# pc_healthypi_move_nRF5340_v3_0.net
KiCad netlist of a schematic drawn in EAGLE
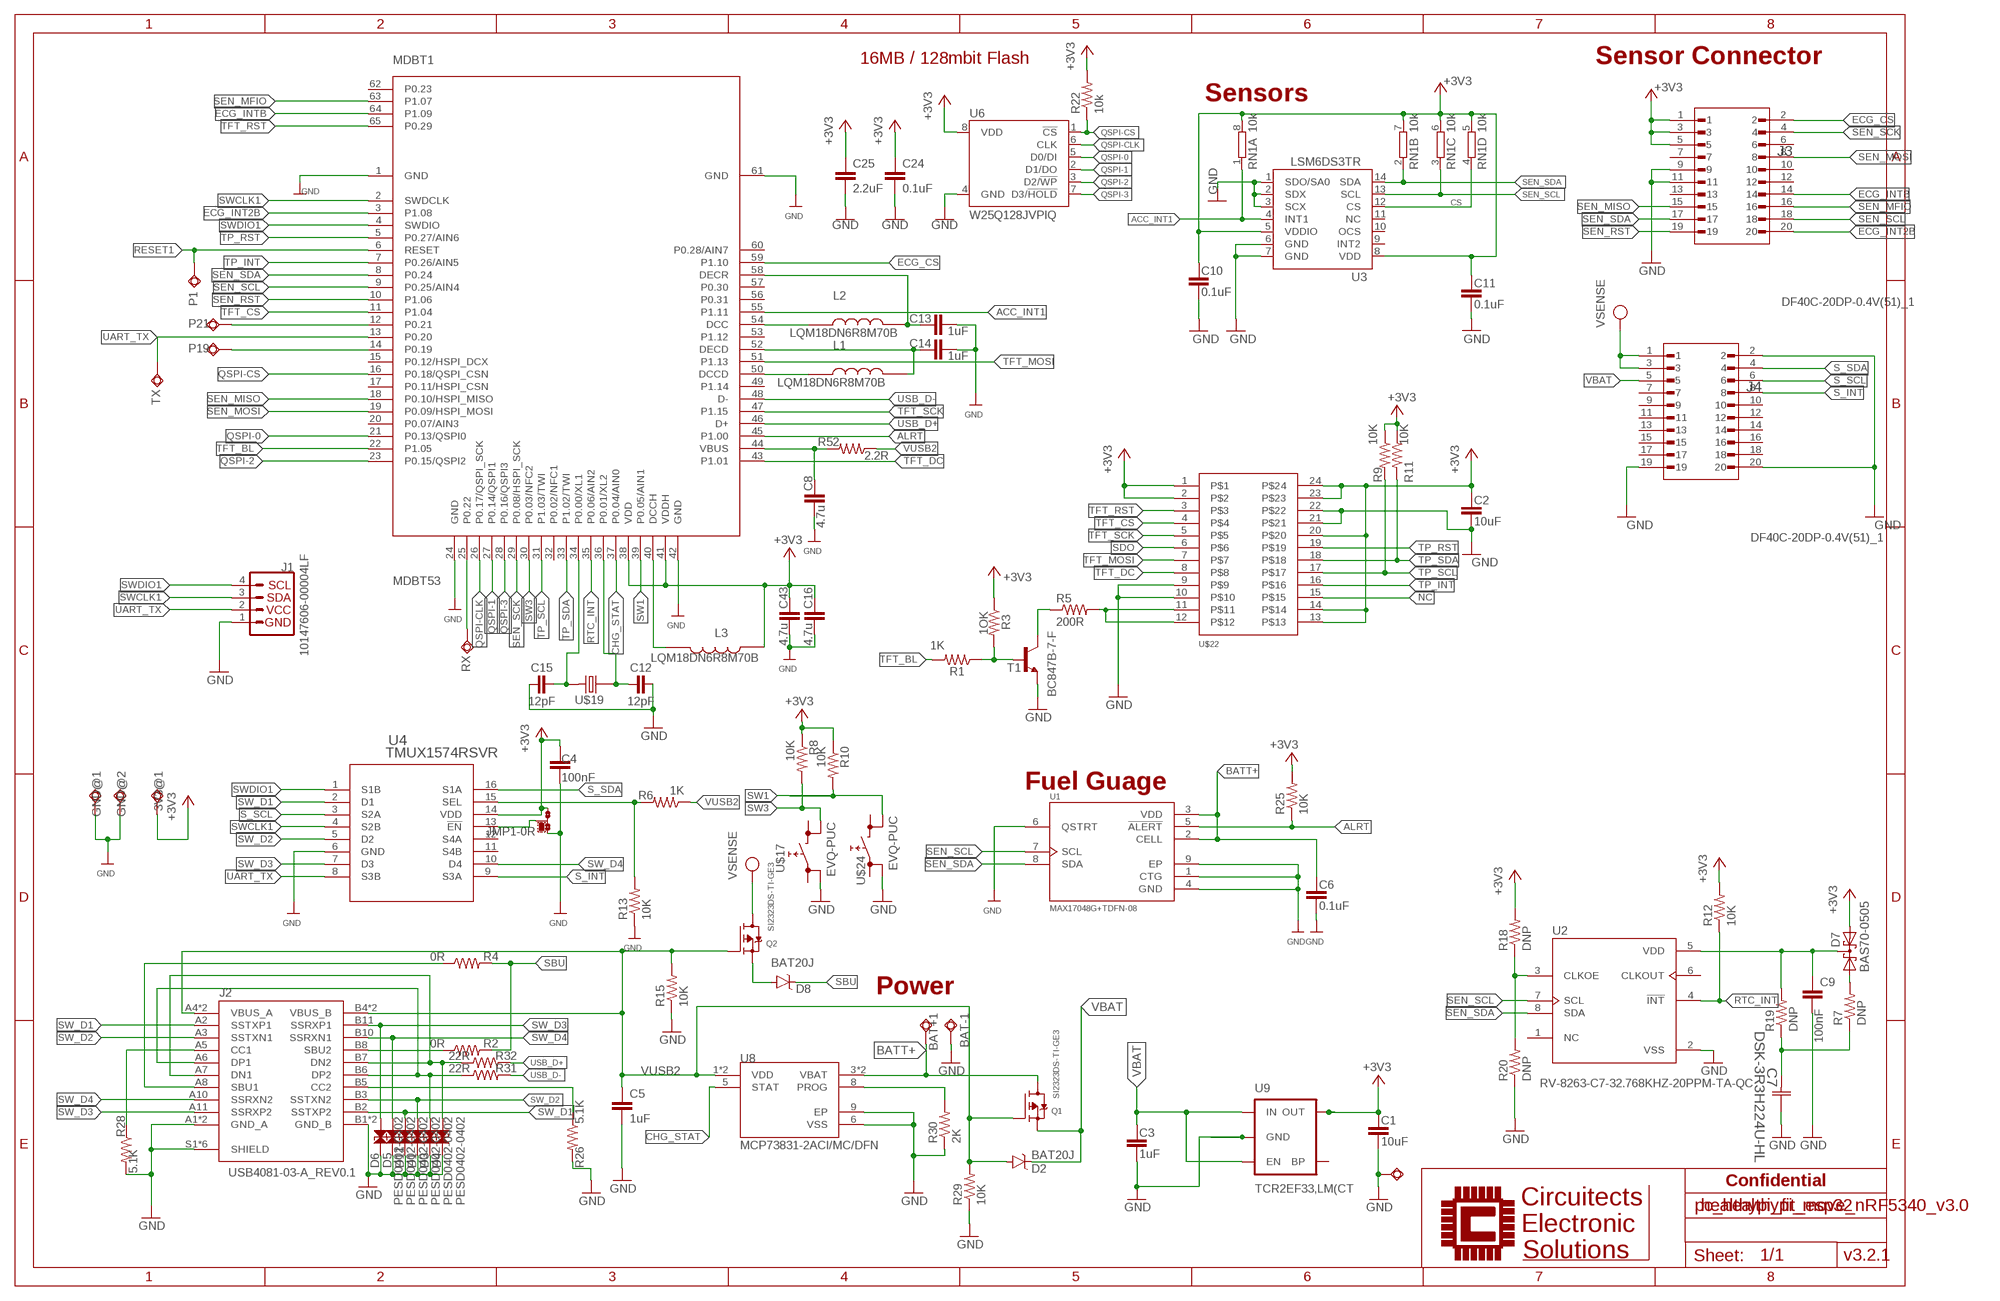
[diagram p0: schematic, sheet 1]

(export (version "E")
  (design (tool "Eeschema 10.0.6"))
  (components
    (comp (ref "3V3@1")
      (value "TPSQTP13SQ")
      (footprint "eagle-import:TP13SQ")
      (libsource (lib "eagle-import") (part "TPSQTP13SQ"))
    )
    (comp (ref "BAT+1")
      (value "TPSQTP13SQ")
      (footprint "eagle-import:TP13SQ")
      (libsource (lib "eagle-import") (part "TPSQTP13SQ"))
    )
    (comp (ref "BAT-1")
      (value "TPSQTP13SQ")
      (footprint "eagle-import:TP13SQ")
      (libsource (lib "eagle-import") (part "TPSQTP13SQ"))
    )
    (comp (ref "C1")
      (value "10uF")
      (footprint "eagle-import:0603@1")
      (libsource (lib "eagle-import") (part "0.1UF-0603-100V-10%"))
    )
    (comp (ref "C2")
      (value "10uF")
      (footprint "eagle-import:0603@1")
      (libsource (lib "eagle-import") (part "0.1UF-0603-100V-10%"))
    )
    (comp (ref "C3")
      (value "1uF")
      (footprint "eagle-import:0402-TIGHT")
      (libsource (lib "eagle-import") (part "0.1UF-0402T-6.3V-10%-X7R"))
    )
    (comp (ref "C4")
      (value "100nF")
      (footprint "eagle-import:0402-TIGHT")
      (libsource (lib "eagle-import") (part "2.2UF-0402_TIGHT-10V-10%-X5R"))
    )
    (comp (ref "C5")
      (value "1uF")
      (footprint "eagle-import:0402-TIGHT")
      (libsource (lib "eagle-import") (part "2.2UF-0402_TIGHT-10V-10%-X5R"))
    )
    (comp (ref "C6")
      (value "0.1uF")
      (footprint "eagle-import:0402-TIGHT")
      (libsource (lib "eagle-import") (part "0.1UF-0402T-6.3V-10%-X7R"))
    )
    (comp (ref "C7")
      (value "DSK-3R3H224U-HL")
      (footprint "eagle-import:CAP_DSK-3R3H224U-HL_ELN")
      (fields (field (name "COPYRIGHT") "Copyright (C) 2023 Ultra Librarian. All rights reserved."))
      (libsource (lib "eagle-import") (part "DSK-3R3H224U-HL"))
    )
    (comp (ref "C8")
      (value "4.7u")
      (footprint "eagle-import:C0402")
      (libsource (lib "eagle-import") (part "C-EUC0402"))
    )
    (comp (ref "C9")
      (value "100nF")
      (footprint "eagle-import:C0402")
      (libsource (lib "eagle-import") (part "C-EUC0402"))
    )
    (comp (ref "C10")
      (value "0.1uF")
      (footprint "eagle-import:0402-TIGHT")
      (libsource (lib "eagle-import") (part "0.1UF-0402T-6.3V-10%-X7R"))
    )
    (comp (ref "C11")
      (value "0.1uF")
      (footprint "eagle-import:0402-TIGHT")
      (libsource (lib "eagle-import") (part "0.1UF-0402T-6.3V-10%-X7R"))
    )
    (comp (ref "C12")
      (value "12pF")
      (footprint "eagle-import:C0402")
      (libsource (lib "eagle-import") (part "CAPACITORS-0402"))
    )
    (comp (ref "C13")
      (value "1uF")
      (footprint "eagle-import:0402-TIGHT")
      (libsource (lib "eagle-import") (part "2.2UF-0402_TIGHT-10V-10%-X5R"))
    )
    (comp (ref "C14")
      (value "1uF")
      (footprint "eagle-import:0402-TIGHT")
      (libsource (lib "eagle-import") (part "2.2UF-0402_TIGHT-10V-10%-X5R"))
    )
    (comp (ref "C15")
      (value "12pF")
      (footprint "eagle-import:C0402")
      (libsource (lib "eagle-import") (part "CAPACITORS-0402"))
    )
    (comp (ref "C16")
      (value "4.7u")
      (footprint "eagle-import:C0402")
      (libsource (lib "eagle-import") (part "C-EUC0402"))
    )
    (comp (ref "C24")
      (value "0.1uF")
      (footprint "eagle-import:0402-TIGHT")
      (libsource (lib "eagle-import") (part "0.1UF-0402T-6.3V-10%-X7R"))
    )
    (comp (ref "C25")
      (value "2.2uF")
      (footprint "eagle-import:0402-TIGHT")
      (libsource (lib "eagle-import") (part "2.2UF-0402_TIGHT-10V-10%-X5R"))
    )
    (comp (ref "C43")
      (value "4.7u")
      (footprint "eagle-import:C0402")
      (libsource (lib "eagle-import") (part "C-EUC0402"))
    )
    (comp (ref "D1")
      (value "PESD0402-0402")
      (footprint "eagle-import:0402")
      (fields
        (field (name "DIGIKEY_PART") "PESD0402-140CT-ND")
        (field (name "MOUSE_PART") "650-PESD0402-140")
      )
      (libsource (lib "eagle-import") (part "PESD0402-0402"))
    )
    (comp (ref "D2")
      (value "BAT20J")
      (footprint "eagle-import:SOD-323")
      (libsource (lib "eagle-import") (part "DIODE-SCHOTTKY-BAT20J"))
    )
    (comp (ref "D3")
      (value "PESD0402-0402")
      (footprint "eagle-import:0402")
      (fields
        (field (name "DIGIKEY_PART") "PESD0402-140CT-ND")
        (field (name "MOUSE_PART") "650-PESD0402-140")
      )
      (libsource (lib "eagle-import") (part "PESD0402-0402"))
    )
    (comp (ref "D4")
      (value "PESD0402-0402")
      (footprint "eagle-import:0402")
      (fields
        (field (name "DIGIKEY_PART") "PESD0402-140CT-ND")
        (field (name "MOUSE_PART") "650-PESD0402-140")
      )
      (libsource (lib "eagle-import") (part "PESD0402-0402"))
    )
    (comp (ref "D5")
      (value "PESD0402-0402")
      (footprint "eagle-import:0402")
      (fields
        (field (name "DIGIKEY_PART") "PESD0402-140CT-ND")
        (field (name "MOUSE_PART") "650-PESD0402-140")
      )
      (libsource (lib "eagle-import") (part "PESD0402-0402"))
    )
    (comp (ref "D6")
      (value "PESD0402-0402")
      (footprint "eagle-import:0402")
      (fields
        (field (name "DIGIKEY_PART") "PESD0402-140CT-ND")
        (field (name "MOUSE_PART") "650-PESD0402-140")
      )
      (libsource (lib "eagle-import") (part "PESD0402-0402"))
    )
    (comp (ref "D7")
      (value "BAS70-0505")
      (footprint "eagle-import:SOT23")
      (fields (field (name "MF") "Diotec") (field (name "MP") "BAS70-05"))
      (libsource (lib "eagle-import") (part "BAS70-0505"))
    )
    (comp (ref "D8")
      (value "BAT20J")
      (footprint "eagle-import:SOD-323")
      (libsource (lib "eagle-import") (part "DIODE-SCHOTTKY-BAT20J"))
    )
    (comp (ref "D11")
      (value "PESD0402-0402")
      (footprint "eagle-import:0402")
      (fields
        (field (name "DIGIKEY_PART") "PESD0402-140CT-ND")
        (field (name "MOUSE_PART") "650-PESD0402-140")
      )
      (libsource (lib "eagle-import") (part "PESD0402-0402"))
    )
    (comp (ref "GND@1")
      (value "TPSQTP13SQ")
      (footprint "eagle-import:TP13SQ")
      (libsource (lib "eagle-import") (part "TPSQTP13SQ"))
    )
    (comp (ref "GND@2")
      (value "TPSQTP13SQ")
      (footprint "eagle-import:TP13SQ")
      (libsource (lib "eagle-import") (part "TPSQTP13SQ"))
    )
    (comp (ref "J1")
      (value "10147606-00004LF")
      (footprint "eagle-import:JST04_1MM_RA")
      (libsource (lib "eagle-import") (part "QWIIC_CONNECTORJS-1MM"))
    )
    (comp (ref "J2")
      (value "USB4081-03-A_REV0.1")
      (footprint "eagle-import:GCT_USB4081-03-A_REV0.1")
      (fields (field (name "MF") "Global Connector Technology") (field (name "MP") "USB4081-03-A"))
      (libsource (lib "eagle-import") (part "USB4081-03-A_REV0.1"))
    )
    (comp (ref "J3")
      (value "DF40C-20DP-0.4V(51)_1")
      (footprint "eagle-import:HRS_DF40C-20DP-0.4V(51)")
      (fields (field (name "MANUFACTURER") "Hirose Electric"))
      (libsource (lib "eagle-import") (part "DF40C-20DP-0.4V(51)_1"))
    )
    (comp (ref "J4")
      (value "DF40C-20DP-0.4V(51)_1")
      (footprint "eagle-import:HRS_DF40C-20DP-0.4V(51)")
      (fields (field (name "MANUFACTURER") "Hirose Electric"))
      (libsource (lib "eagle-import") (part "DF40C-20DP-0.4V(51)_1"))
    )
    (comp (ref "JMP1")
      (value "0R-JUMPB")
      (footprint "eagle-import:B0R-JMP")
      (libsource (lib "eagle-import") (part "0R-JUMPB"))
    )
    (comp (ref "L1")
      (value "LQM18DN6R8M70B")
      (footprint "eagle-import:INDC1608X95N")
      (fields (field (name "MF") "Murata"))
      (libsource (lib "eagle-import") (part "LQM18DN6R8M70B"))
    )
    (comp (ref "L2")
      (value "LQM18DN6R8M70B")
      (footprint "eagle-import:INDC1608X95N")
      (fields (field (name "MF") "Murata"))
      (libsource (lib "eagle-import") (part "LQM18DN6R8M70B"))
    )
    (comp (ref "L3")
      (value "LQM18DN6R8M70B")
      (footprint "eagle-import:INDC1608X95N")
      (fields (field (name "MF") "Murata"))
      (libsource (lib "eagle-import") (part "LQM18DN6R8M70B"))
    )
    (comp (ref "MDBT1")
      (value "MDBT53")
      (footprint "eagle-import:MDBT53")
      (libsource (lib "eagle-import") (part "MDBT53"))
    )
    (comp (ref "P1")
      (value "TPSQTP13SQ")
      (footprint "eagle-import:TP13SQ")
      (libsource (lib "eagle-import") (part "TPSQTP13SQ"))
    )
    (comp (ref "P19")
      (value "TPSQTP13SQ")
      (footprint "eagle-import:TP13SQ")
      (libsource (lib "eagle-import") (part "TPSQTP13SQ"))
    )
    (comp (ref "P21")
      (value "TPSQTP13SQ")
      (footprint "eagle-import:TP13SQ")
      (libsource (lib "eagle-import") (part "TPSQTP13SQ"))
    )
    (comp (ref "Q1")
      (value "SI2323DS-TI-GE3")
      (footprint "eagle-import:SOT23-R")
      (libsource (lib "eagle-import") (part "MOSFET-P"))
    )
    (comp (ref "Q2")
      (value "SI2323DS-TI-GE3")
      (footprint "eagle-import:SOT23-R")
      (libsource (lib "eagle-import") (part "MOSFET-P"))
    )
    (comp (ref "R1")
      (value "200")
      (footprint "eagle-import:R0402")
      (libsource (lib "eagle-import") (part "R-US_R0402"))
    )
    (comp (ref "R2")
      (value "0R")
      (footprint "eagle-import:0402-RES")
      (libsource (lib "eagle-import") (part "RESISTOR0402-RES"))
    )
    (comp (ref "R3")
      (value "200")
      (footprint "eagle-import:R0402")
      (libsource (lib "eagle-import") (part "R-US_R0402"))
    )
    (comp (ref "R4")
      (value "0R")
      (footprint "eagle-import:0402-RES")
      (libsource (lib "eagle-import") (part "RESISTOR0402-RES"))
    )
    (comp (ref "R5")
      (value "200R")
      (footprint "eagle-import:R0402")
      (libsource (lib "eagle-import") (part "R-US_R0402"))
    )
    (comp (ref "R6")
      (value "1K")
      (footprint "eagle-import:0402-RES")
      (libsource (lib "eagle-import") (part "RESISTOR0402-RES"))
    )
    (comp (ref "R7")
      (value "DNP")
      (footprint "eagle-import:R0402")
      (libsource (lib "eagle-import") (part "R-US_R0402"))
    )
    (comp (ref "R8")
      (value "10K")
      (footprint "eagle-import:R0402")
      (libsource (lib "eagle-import") (part "R-US_R0402"))
    )
    (comp (ref "R9")
      (value "10K")
      (footprint "eagle-import:R0402")
      (libsource (lib "eagle-import") (part "R-US_R0402"))
    )
    (comp (ref "R10")
      (value "10K")
      (footprint "eagle-import:R0402")
      (libsource (lib "eagle-import") (part "R-US_R0402"))
    )
    (comp (ref "R11")
      (value "10K")
      (footprint "eagle-import:R0402")
      (libsource (lib "eagle-import") (part "R-US_R0402"))
    )
    (comp (ref "R12")
      (value "10K")
      (footprint "eagle-import:R0402")
      (libsource (lib "eagle-import") (part "R-US_R0402"))
    )
    (comp (ref "R13")
      (value "10K")
      (footprint "eagle-import:R0402")
      (libsource (lib "eagle-import") (part "R-US_R0402"))
    )
    (comp (ref "R15")
      (value "10K")
      (footprint "eagle-import:R0402")
      (libsource (lib "eagle-import") (part "R-US_R0402"))
    )
    (comp (ref "R18")
      (value "DNP")
      (footprint "eagle-import:R0402")
      (libsource (lib "eagle-import") (part "R-US_R0402"))
    )
    (comp (ref "R19")
      (value "DNP")
      (footprint "eagle-import:R0402")
      (libsource (lib "eagle-import") (part "R-US_R0402"))
    )
    (comp (ref "R20")
      (value "DNP")
      (footprint "eagle-import:R0402")
      (libsource (lib "eagle-import") (part "R-US_R0402"))
    )
    (comp (ref "R22")
      (value "10k")
      (footprint "eagle-import:R0402")
      (libsource (lib "eagle-import") (part "R-US_R0402"))
    )
    (comp (ref "R25")
      (value "10K")
      (footprint "eagle-import:0402-RES")
      (libsource (lib "eagle-import") (part "RESISTOR0402-RES"))
    )
    (comp (ref "R26")
      (value "5.1K")
      (footprint "eagle-import:0402-RES")
      (libsource (lib "eagle-import") (part "RESISTOR0402-RES"))
    )
    (comp (ref "R28")
      (value "5.1K")
      (footprint "eagle-import:0402-RES")
      (libsource (lib "eagle-import") (part "RESISTOR0402-RES"))
    )
    (comp (ref "R29")
      (value "10K")
      (footprint "eagle-import:R0402")
      (libsource (lib "eagle-import") (part "R-US_R0402"))
    )
    (comp (ref "R30")
      (value "2K")
      (footprint "eagle-import:R0402")
      (libsource (lib "eagle-import") (part "R-US_R0402"))
    )
    (comp (ref "R31")
      (value "22R")
      (footprint "eagle-import:0402-RES")
      (libsource (lib "eagle-import") (part "RESISTOR0402-RES"))
    )
    (comp (ref "R32")
      (value "22R")
      (footprint "eagle-import:0402-RES")
      (libsource (lib "eagle-import") (part "RESISTOR0402-RES"))
    )
    (comp (ref "R52")
      (value "2.2R")
      (footprint "eagle-import:0402-RES")
      (libsource (lib "eagle-import") (part "RESISTOR0402-RES"))
    )
    (comp (ref "RN1")
      (value "10k")
      (footprint "eagle-import:4X0402ARV341")
      (libsource (lib "eagle-import") (part "4R-N0402ARV341"))
    )
    (comp (ref "RX")
      (value "TPSQTP13SQ")
      (footprint "eagle-import:TP13SQ")
      (libsource (lib "eagle-import") (part "TPSQTP13SQ"))
    )
    (comp (ref "SWIO6")
      (value "TPSQTP11R")
      (footprint "eagle-import:TP11R")
      (libsource (lib "eagle-import") (part "TPSQTP11R"))
    )
    (comp (ref "T1")
      (value "BC847B-7-F")
      (footprint "eagle-import:SOT23-BEC")
      (libsource (lib "eagle-import") (part "-NPN-SOT23-BECMMBT2222ALT1"))
    )
    (comp (ref "TX")
      (value "TPSQTP13SQ")
      (footprint "eagle-import:TP13SQ")
      (libsource (lib "eagle-import") (part "TPSQTP13SQ"))
    )
    (comp (ref "U$17")
      (value "EVQ-PUC")
      (footprint "eagle-import:EVQ-PUC")
      (libsource (lib "eagle-import") (part "EVQ-PUC"))
    )
    (comp (ref "U$19")
      (value "520-327-12.5-34B(32.768KHZ)")
      (footprint "eagle-import:ECX-31B")
      (libsource (lib "eagle-import") (part "ECS-X-34B"))
    )
    (comp (ref "U$22")
      (value "AXT524124")
      (footprint "eagle-import:AXT524124")
      (libsource (lib "eagle-import") (part "AXT524124"))
    )
    (comp (ref "U$24")
      (value "EVQ-PUC")
      (footprint "eagle-import:EVQ-PUC")
      (libsource (lib "eagle-import") (part "EVQ-PUC"))
    )
    (comp (ref "U1")
      (value "MAX17048G+TDFN-08")
      (footprint "eagle-import:SON50P200X200X80-9N")
      (fields (field (name "MF") "Analog Devices") (field (name "MP") "MAX17048G+"))
      (libsource (lib "eagle-import") (part "MAX17048G+TDFN-08"))
    )
    (comp (ref "U2")
      (value "RV-8263-C7-32.768KHZ-20PPM-TA-QC")
      (footprint "eagle-import:IC_RV-8263-C7-32.768KHZ-20PPM-TA-QC")
      (fields (field (name "MF") "Micro Crystal"))
      (libsource (lib "eagle-import") (part "RV-8263-C7-32.768KHZ-20PPM-TA-QC"))
    )
    (comp (ref "U3")
      (value "LSM6DS3TR")
      (footprint "eagle-import:LGA14L")
      (libsource (lib "eagle-import") (part "LSM6DS3"))
    )
    (comp (ref "U4")
      (value "TMUX1574RSVR")
      (footprint "eagle-import:RSV16_TEX")
      (fields (field (name "COPYRIGHT") "Copyright (C) 2024 Ultra Librarian. All rights reserved."))
      (libsource (lib "eagle-import") (part "TMUX1574RSVR"))
    )
    (comp (ref "U6")
      (value "W25Q128JVPIQ")
      (footprint "eagle-import:WSON-8-6X5-SKINNY_CENTERPAD")
      (libsource (lib "eagle-import") (part "W25QXX128MBIT-6X5-SKINNY_CENTER"))
    )
    (comp (ref "U8")
      (value "MCP73831-2ACI/MC/DFN")
      (footprint "eagle-import:SON50P200X300X100-9N")
      (fields (field (name "MF") "Microchip Technology") (field (name "MP") "MCP73831-2ACI/MC"))
      (libsource (lib "eagle-import") (part "MCP73831-2ACI/MC/DFN"))
    )
    (comp (ref "U9")
      (value "TCR2EF33,LM(CT")
      (footprint "eagle-import:SOT23-5")
      (libsource (lib "eagle-import") (part "V_REG_LDOSMD"))
    )
  )
  (nets
    (net (code "1") (name "+3V3") (class "Default")
      (node (ref "3V3@1") (pin "TP") (pinfunction "TP_TP") (pintype "input"))
      (node (ref "C1") (pin "1") (pinfunction "1_1") (pintype "passive"))
      (node (ref "C10") (pin "1") (pinfunction "1_1") (pintype "passive"))
      (node (ref "C11") (pin "1") (pinfunction "1_1") (pintype "passive"))
      (node (ref "C16") (pin "1") (pinfunction "1_1") (pintype "passive"))
      (node (ref "C2") (pin "1") (pinfunction "1_1") (pintype "passive"))
      (node (ref "C24") (pin "1") (pinfunction "1_1") (pintype "passive"))
      (node (ref "C25") (pin "1") (pinfunction "1_1") (pintype "passive"))
      (node (ref "C4") (pin "1") (pinfunction "1_1") (pintype "passive"))
      (node (ref "C43") (pin "1") (pinfunction "1_1") (pintype "passive"))
      (node (ref "D7") (pin "2") (pinfunction "A2_2") (pintype "passive"))
      (node (ref "J3") (pin "1") (pinfunction "1_1") (pintype "passive"))
      (node (ref "J3") (pin "3") (pinfunction "3_3") (pintype "passive"))
      (node (ref "J3") (pin "5") (pinfunction "5_5") (pintype "passive"))
      (node (ref "JMP1") (pin "3") (pinfunction "3_3") (pintype "passive"))
      (node (ref "L3") (pin "1") (pinfunction "1_1") (pintype "passive"))
      (node (ref "MDBT1") (pin "38") (pinfunction "VDD_38") (pintype "bidirectional"))
      (node (ref "MDBT1") (pin "41") (pinfunction "VDDH_41") (pintype "bidirectional"))
      (node (ref "R10") (pin "1") (pinfunction "1_1") (pintype "passive"))
      (node (ref "R11") (pin "1") (pinfunction "1_1") (pintype "passive"))
      (node (ref "R12") (pin "2") (pinfunction "2_2") (pintype "passive"))
      (node (ref "R18") (pin "2") (pinfunction "2_2") (pintype "passive"))
      (node (ref "R22") (pin "2") (pinfunction "2_2") (pintype "passive"))
      (node (ref "R25") (pin "2") (pinfunction "2_2") (pintype "passive"))
      (node (ref "R3") (pin "1") (pinfunction "1_1") (pintype "passive"))
      (node (ref "R8") (pin "1") (pinfunction "1_1") (pintype "passive"))
      (node (ref "R9") (pin "1") (pinfunction "1_1") (pintype "passive"))
      (node (ref "RN1") (pin "5") (pinfunction "2_5") (pintype "passive"))
      (node (ref "RN1") (pin "6") (pinfunction "2_6") (pintype "passive"))
      (node (ref "RN1") (pin "7") (pinfunction "2_7") (pintype "passive"))
      (node (ref "RN1") (pin "8") (pinfunction "2_8") (pintype "passive"))
      (node (ref "U$22") (pin "1") (pinfunction "P$1_1") (pintype "bidirectional"))
      (node (ref "U$22") (pin "13") (pinfunction "P$13_13") (pintype "bidirectional"))
      (node (ref "U$22") (pin "14") (pinfunction "P$14_14") (pintype "bidirectional"))
      (node (ref "U$22") (pin "2") (pinfunction "P$2_2") (pintype "bidirectional"))
      (node (ref "U$22") (pin "20") (pinfunction "P$20_20") (pintype "bidirectional"))
      (node (ref "U$22") (pin "23") (pinfunction "P$23_23") (pintype "bidirectional"))
      (node (ref "U$22") (pin "24") (pinfunction "P$24_24") (pintype "bidirectional"))
      (node (ref "U3") (pin "5") (pinfunction "VDDIO_5") (pintype "bidirectional"))
      (node (ref "U3") (pin "8") (pinfunction "VDD_8") (pintype "bidirectional"))
      (node (ref "U4") (pin "14") (pinfunction "VDD_14") (pintype "power_in"))
      (node (ref "U6") (pin "8") (pinfunction "VDD_8") (pintype "bidirectional"))
      (node (ref "U9") (pin "5") (pinfunction "OUT_5") (pintype "passive"))
    )
    (net (code "2") (name "/CS") (class "Default")
      (node (ref "RN1") (pin "4") (pinfunction "1_4") (pintype "passive"))
      (node (ref "U3") (pin "12") (pinfunction "CS_12") (pintype "bidirectional"))
    )
    (net (code "3") (name "ACC_INT1") (class "Default")
      (node (ref "MDBT1") (pin "55") (pinfunction "P1.11_55") (pintype "bidirectional"))
      (node (ref "RN1") (pin "1") (pinfunction "1_1") (pintype "passive"))
      (node (ref "U3") (pin "4") (pinfunction "INT1_4") (pintype "bidirectional"))
    )
    (net (code "4") (name "ALRT") (class "Default")
      (node (ref "MDBT1") (pin "45") (pinfunction "P1.00_45") (pintype "bidirectional"))
      (node (ref "R25") (pin "1") (pinfunction "1_1") (pintype "passive"))
      (node (ref "U1") (pin "5") (pinfunction "~{ALERT}_5") (pintype "output"))
    )
    (net (code "5") (name "BATT+") (class "Default")
      (node (ref "BAT+1") (pin "TP") (pinfunction "TP_TP") (pintype "input"))
      (node (ref "C6") (pin "1") (pinfunction "1_1") (pintype "passive"))
      (node (ref "Q1") (pin "3") (pinfunction "D_3") (pintype "passive"))
      (node (ref "U1") (pin "2") (pinfunction "CELL_2") (pintype "power_in"))
      (node (ref "U1") (pin "3") (pinfunction "VDD_3") (pintype "power_in"))
      (node (ref "U8") (pin "3") (pinfunction "VBAT_3") (pintype "output"))
      (node (ref "U8") (pin "4") (pinfunction "VBAT_4") (pintype "output"))
    )
    (net (code "6") (name "CHG_STAT") (class "Default")
      (node (ref "MDBT1") (pin "37") (pinfunction "P0.04/AIN0_37") (pintype "bidirectional"))
      (node (ref "U8") (pin "5") (pinfunction "STAT_5") (pintype "output"))
    )
    (net (code "7") (name "ECG_CS") (class "Default")
      (node (ref "J3") (pin "2") (pinfunction "2_2") (pintype "passive"))
      (node (ref "MDBT1") (pin "59") (pinfunction "P1.10_59") (pintype "bidirectional"))
    )
    (net (code "8") (name "ECG_INT2B") (class "Default")
      (node (ref "J3") (pin "20") (pinfunction "20_20") (pintype "passive"))
      (node (ref "MDBT1") (pin "3") (pinfunction "P1.08_3") (pintype "bidirectional"))
    )
    (net (code "9") (name "ECG_INTB") (class "Default")
      (node (ref "J3") (pin "14") (pinfunction "14_14") (pintype "passive"))
      (node (ref "MDBT1") (pin "64") (pinfunction "P1.09_64") (pintype "bidirectional"))
    )
    (net (code "10") (name "GND") (class "Default")
      (node (ref "BAT-1") (pin "TP") (pinfunction "TP_TP") (pintype "input"))
      (node (ref "C1") (pin "2") (pinfunction "2_2") (pintype "passive"))
      (node (ref "C10") (pin "2") (pinfunction "2_2") (pintype "passive"))
      (node (ref "C11") (pin "2") (pinfunction "2_2") (pintype "passive"))
      (node (ref "C12") (pin "2") (pinfunction "2_2") (pintype "passive"))
      (node (ref "C13") (pin "2") (pinfunction "2_2") (pintype "passive"))
      (node (ref "C14") (pin "2") (pinfunction "2_2") (pintype "passive"))
      (node (ref "C15") (pin "1") (pinfunction "1_1") (pintype "passive"))
      (node (ref "C16") (pin "2") (pinfunction "2_2") (pintype "passive"))
      (node (ref "C2") (pin "2") (pinfunction "2_2") (pintype "passive"))
      (node (ref "C24") (pin "2") (pinfunction "2_2") (pintype "passive"))
      (node (ref "C25") (pin "2") (pinfunction "2_2") (pintype "passive"))
      (node (ref "C3") (pin "2") (pinfunction "2_2") (pintype "passive"))
      (node (ref "C4") (pin "2") (pinfunction "2_2") (pintype "passive"))
      (node (ref "C43") (pin "2") (pinfunction "2_2") (pintype "passive"))
      (node (ref "C5") (pin "2") (pinfunction "2_2") (pintype "passive"))
      (node (ref "C6") (pin "2") (pinfunction "2_2") (pintype "passive"))
      (node (ref "C7") (pin "1") (pinfunction "1_1") (pintype "passive"))
      (node (ref "C8") (pin "2") (pinfunction "2_2") (pintype "passive"))
      (node (ref "C9") (pin "2") (pinfunction "2_2") (pintype "passive"))
      (node (ref "D1") (pin "1") (pinfunction "1_1") (pintype "bidirectional"))
      (node (ref "D11") (pin "1") (pinfunction "1_1") (pintype "bidirectional"))
      (node (ref "D3") (pin "1") (pinfunction "1_1") (pintype "bidirectional"))
      (node (ref "D4") (pin "1") (pinfunction "1_1") (pintype "bidirectional"))
      (node (ref "D5") (pin "1") (pinfunction "1_1") (pintype "bidirectional"))
      (node (ref "D6") (pin "1") (pinfunction "1_1") (pintype "bidirectional"))
      (node (ref "GND@1") (pin "TP") (pinfunction "TP_TP") (pintype "input"))
      (node (ref "GND@2") (pin "TP") (pinfunction "TP_TP") (pintype "input"))
      (node (ref "J1") (pin "1") (pinfunction "1_1") (pintype "power_in"))
      (node (ref "J2") (pin "A1") (pinfunction "GND_A_A1") (pintype "power_in"))
      (node (ref "J2") (pin "A12") (pinfunction "GND_A_A12") (pintype "power_in"))
      (node (ref "J2") (pin "B1") (pinfunction "GND_B_B1") (pintype "power_in"))
      (node (ref "J2") (pin "B12") (pinfunction "GND_B_B12") (pintype "power_in"))
      (node (ref "J2") (pin "S1") (pinfunction "SHIELD_S1") (pintype "passive"))
      (node (ref "J2") (pin "S2") (pinfunction "SHIELD_S2") (pintype "passive"))
      (node (ref "J2") (pin "S3") (pinfunction "SHIELD_S3") (pintype "passive"))
      (node (ref "J2") (pin "S4") (pinfunction "SHIELD_S4") (pintype "passive"))
      (node (ref "J2") (pin "S5") (pinfunction "SHIELD_S5") (pintype "passive"))
      (node (ref "J2") (pin "S6") (pinfunction "SHIELD_S6") (pintype "passive"))
      (node (ref "J3") (pin "11") (pinfunction "11_11") (pintype "passive"))
      (node (ref "J3") (pin "9") (pinfunction "9_9") (pintype "passive"))
      (node (ref "J4") (pin "19") (pinfunction "19_19") (pintype "passive"))
      (node (ref "J4") (pin "2") (pinfunction "2_2") (pintype "passive"))
      (node (ref "J4") (pin "20") (pinfunction "20_20") (pintype "passive"))
      (node (ref "JMP1") (pin "1") (pinfunction "1_1") (pintype "passive"))
      (node (ref "MDBT1") (pin "1") (pinfunction "GND_1") (pintype "bidirectional"))
      (node (ref "MDBT1") (pin "24") (pinfunction "GND_24") (pintype "bidirectional"))
      (node (ref "MDBT1") (pin "42") (pinfunction "GND_42") (pintype "bidirectional"))
      (node (ref "MDBT1") (pin "61") (pinfunction "GND_61") (pintype "bidirectional"))
      (node (ref "R13") (pin "1") (pinfunction "1_1") (pintype "passive"))
      (node (ref "R15") (pin "1") (pinfunction "1_1") (pintype "passive"))
      (node (ref "R20") (pin "1") (pinfunction "1_1") (pintype "passive"))
      (node (ref "R26") (pin "2") (pinfunction "2_2") (pintype "passive"))
      (node (ref "R28") (pin "2") (pinfunction "2_2") (pintype "passive"))
      (node (ref "R29") (pin "1") (pinfunction "1_1") (pintype "passive"))
      (node (ref "R30") (pin "1") (pinfunction "1_1") (pintype "passive"))
      (node (ref "SWIO6") (pin "TP") (pinfunction "TP_TP") (pintype "input"))
      (node (ref "T1") (pin "E") (pinfunction "E_E") (pintype "passive"))
      (node (ref "U$17") (pin "3") (pinfunction "0_3") (pintype "passive"))
      (node (ref "U$22") (pin "10") (pinfunction "P$10_10") (pintype "bidirectional"))
      (node (ref "U$22") (pin "21") (pinfunction "P$21_21") (pintype "bidirectional"))
      (node (ref "U$22") (pin "22") (pinfunction "P$22_22") (pintype "bidirectional"))
      (node (ref "U$22") (pin "9") (pinfunction "P$9_9") (pintype "bidirectional"))
      (node (ref "U$24") (pin "3") (pinfunction "0_3") (pintype "passive"))
      (node (ref "U1") (pin "1") (pinfunction "CTG_1") (pintype "power_in"))
      (node (ref "U1") (pin "4") (pinfunction "GND_4") (pintype "power_in"))
      (node (ref "U1") (pin "6") (pinfunction "QSTRT_6") (pintype "input"))
      (node (ref "U1") (pin "9") (pinfunction "EP_9") (pintype "power_in"))
      (node (ref "U2") (pin "2") (pinfunction "VSS_2") (pintype "power_in"))
      (node (ref "U3") (pin "1") (pinfunction "SDO/SA0_1") (pintype "bidirectional"))
      (node (ref "U3") (pin "2") (pinfunction "SDX_2") (pintype "bidirectional"))
      (node (ref "U3") (pin "3") (pinfunction "SCX_3") (pintype "bidirectional"))
      (node (ref "U3") (pin "6") (pinfunction "GND_6") (pintype "bidirectional"))
      (node (ref "U3") (pin "7") (pinfunction "GND_7") (pintype "bidirectional"))
      (node (ref "U4") (pin "6") (pinfunction "GND_6") (pintype "passive"))
      (node (ref "U6") (pin "4") (pinfunction "GND_4") (pintype "bidirectional"))
      (node (ref "U8") (pin "6") (pinfunction "VSS_6") (pintype "power_in"))
      (node (ref "U8") (pin "9") (pinfunction "EP_9") (pintype "power_in"))
      (node (ref "U9") (pin "2") (pinfunction "GND_2") (pintype "input"))
    )
    (net (code "11") (name "NC") (class "Default")
      (node (ref "U$22") (pin "15") (pinfunction "P$15_15") (pintype "bidirectional"))
    )
    (net (code "12") (name "Net-(C7-Pad2)") (class "Default")
      (node (ref "C7") (pin "2") (pinfunction "2_2") (pintype "passive"))
      (node (ref "R19") (pin "1") (pinfunction "1_1") (pintype "passive"))
      (node (ref "R7") (pin "1") (pinfunction "1_1") (pintype "passive"))
    )
    (net (code "13") (name "Net-(D7-A1)") (class "Default")
      (node (ref "D7") (pin "1") (pinfunction "A1_1") (pintype "passive"))
      (node (ref "R7") (pin "2") (pinfunction "2_2") (pintype "passive"))
    )
    (net (code "14") (name "Net-(D7-K1K2)") (class "Default")
      (node (ref "C9") (pin "1") (pinfunction "1_1") (pintype "passive"))
      (node (ref "D7") (pin "3") (pinfunction "K1K2_3") (pintype "passive"))
      (node (ref "R19") (pin "2") (pinfunction "2_2") (pintype "passive"))
      (node (ref "U2") (pin "5") (pinfunction "VDD_5") (pintype "power_in"))
    )
    (net (code "15") (name "Net-(J2-CC1)") (class "Default")
      (node (ref "J2") (pin "A5") (pinfunction "CC1_A5") (pintype "bidirectional"))
      (node (ref "R28") (pin "1") (pinfunction "1_1") (pintype "passive"))
    )
    (net (code "16") (name "Net-(J2-CC2)") (class "Default")
      (node (ref "J2") (pin "B5") (pinfunction "CC2_B5") (pintype "bidirectional"))
      (node (ref "R26") (pin "1") (pinfunction "1_1") (pintype "passive"))
    )
    (net (code "17") (name "Net-(J2-DN1)") (class "Default")
      (node (ref "D4") (pin "2") (pinfunction "2_2") (pintype "bidirectional"))
      (node (ref "J2") (pin "A7") (pinfunction "DN1_A7") (pintype "bidirectional"))
      (node (ref "J2") (pin "B7") (pinfunction "DN2_B7") (pintype "bidirectional"))
      (node (ref "R32") (pin "1") (pinfunction "1_1") (pintype "passive"))
    )
    (net (code "18") (name "Net-(J2-DP1)") (class "Default")
      (node (ref "D3") (pin "2") (pinfunction "2_2") (pintype "bidirectional"))
      (node (ref "J2") (pin "A6") (pinfunction "DP1_A6") (pintype "bidirectional"))
      (node (ref "J2") (pin "B6") (pinfunction "DP2_B6") (pintype "bidirectional"))
      (node (ref "R31") (pin "1") (pinfunction "1_1") (pintype "passive"))
    )
    (net (code "19") (name "Net-(J2-SBU1)") (class "Default")
      (node (ref "J2") (pin "A8") (pinfunction "SBU1_A8") (pintype "bidirectional"))
      (node (ref "R4") (pin "1") (pinfunction "1_1") (pintype "passive"))
    )
    (net (code "20") (name "Net-(J2-SBU2)") (class "Default")
      (node (ref "J2") (pin "B8") (pinfunction "SBU2_B8") (pintype "bidirectional"))
      (node (ref "R2") (pin "1") (pinfunction "1_1") (pintype "passive"))
    )
    (net (code "21") (name "Net-(MDBT1-DCC)") (class "Default")
      (node (ref "L2") (pin "1") (pinfunction "1_1") (pintype "passive"))
      (node (ref "MDBT1") (pin "54") (pinfunction "DCC_54") (pintype "bidirectional"))
    )
    (net (code "22") (name "Net-(MDBT1-DCCD)") (class "Default")
      (node (ref "L1") (pin "1") (pinfunction "1_1") (pintype "passive"))
      (node (ref "MDBT1") (pin "50") (pinfunction "DCCD_50") (pintype "bidirectional"))
    )
    (net (code "23") (name "Net-(MDBT1-DCCH)") (class "Default")
      (node (ref "L3") (pin "2") (pinfunction "2_2") (pintype "passive"))
      (node (ref "MDBT1") (pin "40") (pinfunction "DCCH_40") (pintype "bidirectional"))
    )
    (net (code "24") (name "Net-(MDBT1-DECD)") (class "Default")
      (node (ref "C14") (pin "1") (pinfunction "1_1") (pintype "passive"))
      (node (ref "L1") (pin "2") (pinfunction "2_2") (pintype "passive"))
      (node (ref "MDBT1") (pin "52") (pinfunction "DECD_52") (pintype "bidirectional"))
    )
    (net (code "25") (name "Net-(MDBT1-DECR)") (class "Default")
      (node (ref "C13") (pin "1") (pinfunction "1_1") (pintype "passive"))
      (node (ref "L2") (pin "2") (pinfunction "2_2") (pintype "passive"))
      (node (ref "MDBT1") (pin "58") (pinfunction "DECR_58") (pintype "bidirectional"))
    )
    (net (code "26") (name "Net-(MDBT1-P0.00{slash}XL1)") (class "Default")
      (node (ref "C15") (pin "2") (pinfunction "2_2") (pintype "passive"))
      (node (ref "MDBT1") (pin "34") (pinfunction "P0.00/XL1_34") (pintype "bidirectional"))
      (node (ref "U$19") (pin "P$2") (pinfunction "2_P$2") (pintype "passive"))
    )
    (net (code "27") (name "Net-(MDBT1-P0.01{slash}XL2)") (class "Default")
      (node (ref "C12") (pin "1") (pinfunction "1_1") (pintype "passive"))
      (node (ref "MDBT1") (pin "36") (pinfunction "P0.01/XL2_36") (pintype "bidirectional"))
      (node (ref "U$19") (pin "P$1") (pinfunction "1_P$1") (pintype "passive"))
    )
    (net (code "28") (name "Net-(MDBT1-P0.19)") (class "Default")
      (node (ref "MDBT1") (pin "14") (pinfunction "P0.19_14") (pintype "bidirectional"))
      (node (ref "P19") (pin "TP") (pinfunction "TP_TP") (pintype "input"))
    )
    (net (code "29") (name "Net-(MDBT1-P0.21)") (class "Default")
      (node (ref "MDBT1") (pin "12") (pinfunction "P0.21_12") (pintype "bidirectional"))
      (node (ref "P21") (pin "TP") (pinfunction "TP_TP") (pintype "input"))
    )
    (net (code "30") (name "Net-(MDBT1-P0.22)") (class "Default")
      (node (ref "MDBT1") (pin "25") (pinfunction "P0.22_25") (pintype "bidirectional"))
      (node (ref "RX") (pin "TP") (pinfunction "TP_TP") (pintype "input"))
    )
    (net (code "31") (name "Net-(MDBT1-VBUS)") (class "Default")
      (node (ref "C8") (pin "1") (pinfunction "1_1") (pintype "passive"))
      (node (ref "MDBT1") (pin "44") (pinfunction "VBUS_44") (pintype "bidirectional"))
      (node (ref "R52") (pin "2") (pinfunction "2_2") (pintype "passive"))
    )
    (net (code "32") (name "Net-(Q2-S)") (class "Default")
      (node (ref "D8") (pin "A") (pinfunction "A_A") (pintype "passive"))
      (node (ref "Q2") (pin "2") (pinfunction "S_2") (pintype "passive"))
    )
    (net (code "33") (name "Net-(R1-Pad1)") (class "Default")
      (node (ref "R1") (pin "1") (pinfunction "1_1") (pintype "passive"))
      (node (ref "R3") (pin "2") (pinfunction "2_2") (pintype "passive"))
      (node (ref "T1") (pin "B") (pinfunction "B_B") (pintype "passive"))
    )
    (net (code "34") (name "Net-(R5-Pad1)") (class "Default")
      (node (ref "R5") (pin "1") (pinfunction "1_1") (pintype "passive"))
      (node (ref "T1") (pin "C") (pinfunction "C_C") (pintype "passive"))
    )
    (net (code "35") (name "Net-(U$22-P$11)") (class "Default")
      (node (ref "R5") (pin "2") (pinfunction "2_2") (pintype "passive"))
      (node (ref "U$22") (pin "11") (pinfunction "P$11_11") (pintype "bidirectional"))
      (node (ref "U$22") (pin "12") (pinfunction "P$12_12") (pintype "bidirectional"))
    )
    (net (code "36") (name "Net-(U2-CLKOE)") (class "Default")
      (node (ref "R18") (pin "1") (pinfunction "1_1") (pintype "passive"))
      (node (ref "R20") (pin "2") (pinfunction "2_2") (pintype "passive"))
      (node (ref "U2") (pin "3") (pinfunction "CLKOE_3") (pintype "input"))
    )
    (net (code "37") (name "Net-(U4-SEL)") (class "Default")
      (node (ref "R13") (pin "2") (pinfunction "2_2") (pintype "passive"))
      (node (ref "R6") (pin "2") (pinfunction "2_2") (pintype "passive"))
      (node (ref "U4") (pin "15") (pinfunction "SEL_15") (pintype "passive"))
    )
    (net (code "38") (name "Net-(U4-~{EN})") (class "Default")
      (node (ref "JMP1") (pin "2") (pinfunction "2_2") (pintype "passive"))
      (node (ref "U4") (pin "13") (pinfunction "~{EN}_13") (pintype "passive"))
    )
    (net (code "39") (name "Net-(U8-PROG)") (class "Default")
      (node (ref "R30") (pin "2") (pinfunction "2_2") (pintype "passive"))
      (node (ref "U8") (pin "8") (pinfunction "PROG_8") (pintype "input"))
    )
    (net (code "40") (name "QSPI-0") (class "Default")
      (node (ref "MDBT1") (pin "21") (pinfunction "P0.13/QSPI0_21") (pintype "bidirectional"))
      (node (ref "U6") (pin "5") (pinfunction "D0/DI_5") (pintype "bidirectional"))
    )
    (net (code "41") (name "QSPI-1") (class "Default")
      (node (ref "MDBT1") (pin "27") (pinfunction "P0.14/QSPI1_27") (pintype "bidirectional"))
      (node (ref "U6") (pin "2") (pinfunction "D1/DO_2") (pintype "bidirectional"))
    )
    (net (code "42") (name "QSPI-2") (class "Default")
      (node (ref "MDBT1") (pin "23") (pinfunction "P0.15/QSPI2_23") (pintype "bidirectional"))
      (node (ref "U6") (pin "3") (pinfunction "D2/~{WP}_3") (pintype "bidirectional"))
    )
    (net (code "43") (name "QSPI-3") (class "Default")
      (node (ref "MDBT1") (pin "28") (pinfunction "P0.16/QSPI3_28") (pintype "bidirectional"))
      (node (ref "U6") (pin "7") (pinfunction "D3/~{HOLD}_7") (pintype "bidirectional"))
    )
    (net (code "44") (name "QSPI-CLK") (class "Default")
      (node (ref "MDBT1") (pin "26") (pinfunction "P0.17/QSPI_SCK_26") (pintype "bidirectional"))
      (node (ref "U6") (pin "6") (pinfunction "CLK_6") (pintype "bidirectional"))
    )
    (net (code "45") (name "QSPI-CS") (class "Default")
      (node (ref "MDBT1") (pin "16") (pinfunction "P0.18/QSPI_CSN_16") (pintype "bidirectional"))
      (node (ref "R22") (pin "1") (pinfunction "1_1") (pintype "passive"))
      (node (ref "U6") (pin "1") (pinfunction "~{CS}_1") (pintype "bidirectional"))
    )
    (net (code "46") (name "RESET1") (class "Default")
      (node (ref "MDBT1") (pin "6") (pinfunction "RESET_6") (pintype "bidirectional"))
      (node (ref "P1") (pin "TP") (pinfunction "TP_TP") (pintype "input"))
    )
    (net (code "47") (name "RTC_INT") (class "Default")
      (node (ref "MDBT1") (pin "35") (pinfunction "P0.06/AIN2_35") (pintype "bidirectional"))
      (node (ref "R12") (pin "1") (pinfunction "1_1") (pintype "passive"))
      (node (ref "U2") (pin "4") (pinfunction "~{INT}_4") (pintype "output"))
    )
    (net (code "48") (name "SBU") (class "Default")
      (node (ref "D8") (pin "C") (pinfunction "C_C") (pintype "passive"))
      (node (ref "R2") (pin "2") (pinfunction "2_2") (pintype "passive"))
      (node (ref "R4") (pin "2") (pinfunction "2_2") (pintype "passive"))
    )
    (net (code "49") (name "SDO") (class "Default")
      (node (ref "U$22") (pin "6") (pinfunction "P$6_6") (pintype "bidirectional"))
    )
    (net (code "50") (name "SEN_MFIO") (class "Default")
      (node (ref "J3") (pin "16") (pinfunction "16_16") (pintype "passive"))
      (node (ref "MDBT1") (pin "63") (pinfunction "P1.07_63") (pintype "bidirectional"))
    )
    (net (code "51") (name "SEN_MISO") (class "Default")
      (node (ref "J3") (pin "15") (pinfunction "15_15") (pintype "passive"))
      (node (ref "MDBT1") (pin "18") (pinfunction "P0.10/HSPI_MISO_18") (pintype "bidirectional"))
    )
    (net (code "52") (name "SEN_MOSI") (class "Default")
      (node (ref "J3") (pin "8") (pinfunction "8_8") (pintype "passive"))
      (node (ref "MDBT1") (pin "19") (pinfunction "P0.09/HSPI_MOSI_19") (pintype "bidirectional"))
    )
    (net (code "53") (name "SEN_RST") (class "Default")
      (node (ref "J3") (pin "19") (pinfunction "19_19") (pintype "passive"))
      (node (ref "MDBT1") (pin "10") (pinfunction "P1.06_10") (pintype "bidirectional"))
    )
    (net (code "54") (name "SEN_SCK") (class "Default")
      (node (ref "J3") (pin "4") (pinfunction "4_4") (pintype "passive"))
      (node (ref "MDBT1") (pin "29") (pinfunction "P0.08/HSPI_SCK_29") (pintype "bidirectional"))
    )
    (net (code "55") (name "SEN_SCL") (class "Default")
      (node (ref "J3") (pin "18") (pinfunction "18_18") (pintype "passive"))
      (node (ref "MDBT1") (pin "9") (pinfunction "P0.25/AIN4_9") (pintype "bidirectional"))
      (node (ref "RN1") (pin "3") (pinfunction "1_3") (pintype "passive"))
      (node (ref "U1") (pin "7") (pinfunction "SCL_7") (pintype "input"))
      (node (ref "U2") (pin "7") (pinfunction "SCL_7") (pintype "input"))
      (node (ref "U3") (pin "13") (pinfunction "SCL_13") (pintype "bidirectional"))
    )
    (net (code "56") (name "SEN_SDA") (class "Default")
      (node (ref "J3") (pin "17") (pinfunction "17_17") (pintype "passive"))
      (node (ref "MDBT1") (pin "8") (pinfunction "P0.24_8") (pintype "bidirectional"))
      (node (ref "RN1") (pin "2") (pinfunction "1_2") (pintype "passive"))
      (node (ref "U1") (pin "8") (pinfunction "SDA_8") (pintype "bidirectional"))
      (node (ref "U2") (pin "8") (pinfunction "SDA_8") (pintype "bidirectional"))
      (node (ref "U3") (pin "14") (pinfunction "SDA_14") (pintype "bidirectional"))
    )
    (net (code "57") (name "SW1") (class "Default")
      (node (ref "MDBT1") (pin "39") (pinfunction "P0.05/AIN1_39") (pintype "bidirectional"))
      (node (ref "R10") (pin "2") (pinfunction "2_2") (pintype "passive"))
      (node (ref "U$24") (pin "2") (pinfunction "1_2") (pintype "passive"))
    )
    (net (code "58") (name "SW3") (class "Default")
      (node (ref "MDBT1") (pin "30") (pinfunction "P0.03/NFC2_30") (pintype "bidirectional"))
      (node (ref "R8") (pin "2") (pinfunction "2_2") (pintype "passive"))
      (node (ref "U$17") (pin "2") (pinfunction "1_2") (pintype "passive"))
    )
    (net (code "59") (name "SWCLK1") (class "Default")
      (node (ref "J1") (pin "3") (pinfunction "3_3") (pintype "passive"))
      (node (ref "MDBT1") (pin "2") (pinfunction "SWDCLK_2") (pintype "bidirectional"))
      (node (ref "U4") (pin "4") (pinfunction "S2B_4") (pintype "bidirectional"))
    )
    (net (code "60") (name "SWDIO1") (class "Default")
      (node (ref "J1") (pin "4") (pinfunction "4_4") (pintype "passive"))
      (node (ref "MDBT1") (pin "4") (pinfunction "SWDIO_4") (pintype "bidirectional"))
      (node (ref "U4") (pin "1") (pinfunction "S1B_1") (pintype "bidirectional"))
    )
    (net (code "61") (name "SW_D1") (class "Default")
      (node (ref "D11") (pin "2") (pinfunction "2_2") (pintype "bidirectional"))
      (node (ref "J2") (pin "A2") (pinfunction "SSTXP1_A2") (pintype "bidirectional"))
      (node (ref "J2") (pin "B2") (pinfunction "SSTXP2_B2") (pintype "bidirectional"))
      (node (ref "U4") (pin "2") (pinfunction "D1_2") (pintype "bidirectional"))
    )
    (net (code "62") (name "SW_D2") (class "Default")
      (node (ref "D1") (pin "2") (pinfunction "2_2") (pintype "bidirectional"))
      (node (ref "J2") (pin "A3") (pinfunction "SSTXN1_A3") (pintype "bidirectional"))
      (node (ref "J2") (pin "B3") (pinfunction "SSTXN2_B3") (pintype "bidirectional"))
      (node (ref "U4") (pin "5") (pinfunction "D2_5") (pintype "bidirectional"))
    )
    (net (code "63") (name "SW_D3") (class "Default")
      (node (ref "D6") (pin "2") (pinfunction "2_2") (pintype "bidirectional"))
      (node (ref "J2") (pin "A11") (pinfunction "SSRXP2_A11") (pintype "bidirectional"))
      (node (ref "J2") (pin "B11") (pinfunction "SSRXP1_B11") (pintype "bidirectional"))
      (node (ref "U4") (pin "7") (pinfunction "D3_7") (pintype "bidirectional"))
    )
    (net (code "64") (name "SW_D4") (class "Default")
      (node (ref "D5") (pin "2") (pinfunction "2_2") (pintype "bidirectional"))
      (node (ref "J2") (pin "A10") (pinfunction "SSRXN2_A10") (pintype "bidirectional"))
      (node (ref "J2") (pin "B10") (pinfunction "SSRXN1_B10") (pintype "bidirectional"))
      (node (ref "U4") (pin "10") (pinfunction "D4_10") (pintype "bidirectional"))
    )
    (net (code "65") (name "S_INT") (class "Default")
      (node (ref "J4") (pin "8") (pinfunction "8_8") (pintype "passive"))
      (node (ref "U4") (pin "9") (pinfunction "S3A_9") (pintype "bidirectional"))
    )
    (net (code "66") (name "S_SCL") (class "Default")
      (node (ref "J4") (pin "6") (pinfunction "6_6") (pintype "passive"))
      (node (ref "U4") (pin "3") (pinfunction "S2A_3") (pintype "bidirectional"))
    )
    (net (code "67") (name "S_SDA") (class "Default")
      (node (ref "J4") (pin "4") (pinfunction "4_4") (pintype "passive"))
      (node (ref "U4") (pin "16") (pinfunction "S1A_16") (pintype "bidirectional"))
    )
    (net (code "68") (name "TFT_BL") (class "Default")
      (node (ref "MDBT1") (pin "22") (pinfunction "P1.05_22") (pintype "bidirectional"))
      (node (ref "R1") (pin "2") (pinfunction "2_2") (pintype "passive"))
    )
    (net (code "69") (name "TFT_CS") (class "Default")
      (node (ref "MDBT1") (pin "11") (pinfunction "P1.04_11") (pintype "bidirectional"))
      (node (ref "U$22") (pin "4") (pinfunction "P$4_4") (pintype "bidirectional"))
    )
    (net (code "70") (name "TFT_DC") (class "Default")
      (node (ref "MDBT1") (pin "43") (pinfunction "P1.01_43") (pintype "bidirectional"))
      (node (ref "U$22") (pin "8") (pinfunction "P$8_8") (pintype "bidirectional"))
    )
    (net (code "71") (name "TFT_MOSI") (class "Default")
      (node (ref "MDBT1") (pin "51") (pinfunction "P1.13_51") (pintype "bidirectional"))
      (node (ref "U$22") (pin "7") (pinfunction "P$7_7") (pintype "bidirectional"))
    )
    (net (code "72") (name "TFT_RST") (class "Default")
      (node (ref "MDBT1") (pin "65") (pinfunction "P0.29_65") (pintype "bidirectional"))
      (node (ref "U$22") (pin "3") (pinfunction "P$3_3") (pintype "bidirectional"))
    )
    (net (code "73") (name "TFT_SCK") (class "Default")
      (node (ref "MDBT1") (pin "47") (pinfunction "P1.15_47") (pintype "bidirectional"))
      (node (ref "U$22") (pin "5") (pinfunction "P$5_5") (pintype "bidirectional"))
    )
    (net (code "74") (name "TP_INT") (class "Default")
      (node (ref "MDBT1") (pin "7") (pinfunction "P0.26/AIN5_7") (pintype "bidirectional"))
      (node (ref "U$22") (pin "16") (pinfunction "P$16_16") (pintype "bidirectional"))
    )
    (net (code "75") (name "TP_RST") (class "Default")
      (node (ref "MDBT1") (pin "5") (pinfunction "P0.27/AIN6_5") (pintype "bidirectional"))
      (node (ref "U$22") (pin "19") (pinfunction "P$19_19") (pintype "bidirectional"))
    )
    (net (code "76") (name "TP_SCL") (class "Default")
      (node (ref "MDBT1") (pin "31") (pinfunction "P1.03/TWI_31") (pintype "bidirectional"))
      (node (ref "R9") (pin "2") (pinfunction "2_2") (pintype "passive"))
      (node (ref "U$22") (pin "17") (pinfunction "P$17_17") (pintype "bidirectional"))
    )
    (net (code "77") (name "TP_SDA") (class "Default")
      (node (ref "MDBT1") (pin "33") (pinfunction "P1.02/TWI_33") (pintype "bidirectional"))
      (node (ref "R11") (pin "2") (pinfunction "2_2") (pintype "passive"))
      (node (ref "U$22") (pin "18") (pinfunction "P$18_18") (pintype "bidirectional"))
    )
    (net (code "78") (name "UART_TX") (class "Default")
      (node (ref "J1") (pin "2") (pinfunction "2_2") (pintype "power_in"))
      (node (ref "MDBT1") (pin "13") (pinfunction "P0.20_13") (pintype "bidirectional"))
      (node (ref "TX") (pin "TP") (pinfunction "TP_TP") (pintype "input"))
      (node (ref "U4") (pin "8") (pinfunction "S3B_8") (pintype "bidirectional"))
    )
    (net (code "79") (name "USB_D+") (class "Default")
      (node (ref "MDBT1") (pin "46") (pinfunction "D+_46") (pintype "bidirectional"))
      (node (ref "R32") (pin "2") (pinfunction "2_2") (pintype "passive"))
    )
    (net (code "80") (name "USB_D-") (class "Default")
      (node (ref "MDBT1") (pin "48") (pinfunction "D-_48") (pintype "bidirectional"))
      (node (ref "R31") (pin "2") (pinfunction "2_2") (pintype "passive"))
    )
    (net (code "81") (name "VBAT") (class "Default")
      (node (ref "C3") (pin "1") (pinfunction "1_1") (pintype "passive"))
      (node (ref "D2") (pin "C") (pinfunction "C_C") (pintype "passive"))
      (node (ref "J4") (pin "5") (pinfunction "5_5") (pintype "passive"))
      (node (ref "Q1") (pin "2") (pinfunction "S_2") (pintype "passive"))
      (node (ref "U9") (pin "1") (pinfunction "IN_1") (pintype "input"))
      (node (ref "U9") (pin "3") (pinfunction "EN_3") (pintype "input"))
    )
    (net (code "82") (name "VSENSE") (class "Default")
      (node (ref "J4") (pin "1") (pinfunction "1_1") (pintype "passive"))
      (node (ref "J4") (pin "3") (pinfunction "3_3") (pintype "passive"))
      (node (ref "Q2") (pin "3") (pinfunction "D_3") (pintype "passive"))
    )
    (net (code "83") (name "VUSB2") (class "Default")
      (node (ref "C5") (pin "1") (pinfunction "1_1") (pintype "passive"))
      (node (ref "D2") (pin "A") (pinfunction "A_A") (pintype "passive"))
      (node (ref "J2") (pin "A4") (pinfunction "VBUS_A_A4") (pintype "power_in"))
      (node (ref "J2") (pin "A9") (pinfunction "VBUS_A_A9") (pintype "power_in"))
      (node (ref "J2") (pin "B4") (pinfunction "VBUS_B_B4") (pintype "power_in"))
      (node (ref "J2") (pin "B9") (pinfunction "VBUS_B_B9") (pintype "power_in"))
      (node (ref "Q1") (pin "1") (pinfunction "G_1") (pintype "passive"))
      (node (ref "Q2") (pin "1") (pinfunction "G_1") (pintype "passive"))
      (node (ref "R15") (pin "2") (pinfunction "2_2") (pintype "passive"))
      (node (ref "R29") (pin "2") (pinfunction "2_2") (pintype "passive"))
      (node (ref "R52") (pin "1") (pinfunction "1_1") (pintype "passive"))
      (node (ref "R6") (pin "1") (pinfunction "1_1") (pintype "passive"))
      (node (ref "U8") (pin "1") (pinfunction "VDD_1") (pintype "power_in"))
      (node (ref "U8") (pin "2") (pinfunction "VDD_2") (pintype "power_in"))
    )
    (net (code "84") (name "unconnected-(J3-Pad6)") (class "Default")
      (node (ref "J3") (pin "6") (pinfunction "6_6") (pintype "passive"))
    )
    (net (code "85") (name "unconnected-(J3-Pad7)") (class "Default")
      (node (ref "J3") (pin "7") (pinfunction "7_7") (pintype "passive"))
    )
    (net (code "86") (name "unconnected-(J3-Pad10)") (class "Default")
      (node (ref "J3") (pin "10") (pinfunction "10_10") (pintype "passive"))
    )
    (net (code "87") (name "unconnected-(J3-Pad12)") (class "Default")
      (node (ref "J3") (pin "12") (pinfunction "12_12") (pintype "passive"))
    )
    (net (code "88") (name "unconnected-(J3-Pad13)") (class "Default")
      (node (ref "J3") (pin "13") (pinfunction "13_13") (pintype "passive"))
    )
    (net (code "89") (name "unconnected-(J4-Pad7)") (class "Default")
      (node (ref "J4") (pin "7") (pinfunction "7_7") (pintype "passive"))
    )
    (net (code "90") (name "unconnected-(J4-Pad9)") (class "Default")
      (node (ref "J4") (pin "9") (pinfunction "9_9") (pintype "passive"))
    )
    (net (code "91") (name "unconnected-(J4-Pad10)") (class "Default")
      (node (ref "J4") (pin "10") (pinfunction "10_10") (pintype "passive"))
    )
    (net (code "92") (name "unconnected-(J4-Pad11)") (class "Default")
      (node (ref "J4") (pin "11") (pinfunction "11_11") (pintype "passive"))
    )
    (net (code "93") (name "unconnected-(J4-Pad12)") (class "Default")
      (node (ref "J4") (pin "12") (pinfunction "12_12") (pintype "passive"))
    )
    (net (code "94") (name "unconnected-(J4-Pad13)") (class "Default")
      (node (ref "J4") (pin "13") (pinfunction "13_13") (pintype "passive"))
    )
    (net (code "95") (name "unconnected-(J4-Pad14)") (class "Default")
      (node (ref "J4") (pin "14") (pinfunction "14_14") (pintype "passive"))
    )
    (net (code "96") (name "unconnected-(J4-Pad15)") (class "Default")
      (node (ref "J4") (pin "15") (pinfunction "15_15") (pintype "passive"))
    )
    (net (code "97") (name "unconnected-(J4-Pad16)") (class "Default")
      (node (ref "J4") (pin "16") (pinfunction "16_16") (pintype "passive"))
    )
    (net (code "98") (name "unconnected-(J4-Pad17)") (class "Default")
      (node (ref "J4") (pin "17") (pinfunction "17_17") (pintype "passive"))
    )
    (net (code "99") (name "unconnected-(J4-Pad18)") (class "Default")
      (node (ref "J4") (pin "18") (pinfunction "18_18") (pintype "passive"))
    )
    (net (code "100") (name "unconnected-(MDBT1-P0.02{slash}NFC1-Pad32)") (class "Default")
      (node (ref "MDBT1") (pin "32") (pinfunction "P0.02/NFC1_32") (pintype "bidirectional"))
    )
    (net (code "101") (name "unconnected-(MDBT1-P0.07{slash}AIN3-Pad20)") (class "Default")
      (node (ref "MDBT1") (pin "20") (pinfunction "P0.07/AIN3_20") (pintype "bidirectional"))
    )
    (net (code "102") (name "unconnected-(MDBT1-P0.11{slash}HSPI_CSN-Pad17)") (class "Default")
      (node (ref "MDBT1") (pin "17") (pinfunction "P0.11/HSPI_CSN_17") (pintype "bidirectional"))
    )
    (net (code "103") (name "unconnected-(MDBT1-P0.12{slash}HSPI_DCX-Pad15)") (class "Default")
      (node (ref "MDBT1") (pin "15") (pinfunction "P0.12/HSPI_DCX_15") (pintype "bidirectional"))
    )
    (net (code "104") (name "unconnected-(MDBT1-P0.23-Pad62)") (class "Default")
      (node (ref "MDBT1") (pin "62") (pinfunction "P0.23_62") (pintype "bidirectional"))
    )
    (net (code "105") (name "unconnected-(MDBT1-P0.28{slash}AIN7-Pad60)") (class "Default")
      (node (ref "MDBT1") (pin "60") (pinfunction "P0.28/AIN7_60") (pintype "bidirectional"))
    )
    (net (code "106") (name "unconnected-(MDBT1-P0.30-Pad57)") (class "Default")
      (node (ref "MDBT1") (pin "57") (pinfunction "P0.30_57") (pintype "bidirectional"))
    )
    (net (code "107") (name "unconnected-(MDBT1-P0.31-Pad56)") (class "Default")
      (node (ref "MDBT1") (pin "56") (pinfunction "P0.31_56") (pintype "bidirectional"))
    )
    (net (code "108") (name "unconnected-(MDBT1-P1.12-Pad53)") (class "Default")
      (node (ref "MDBT1") (pin "53") (pinfunction "P1.12_53") (pintype "bidirectional"))
    )
    (net (code "109") (name "unconnected-(MDBT1-P1.14-Pad49)") (class "Default")
      (node (ref "MDBT1") (pin "49") (pinfunction "P1.14_49") (pintype "bidirectional"))
    )
    (net (code "110") (name "unconnected-(U$17-0-Pad1)") (class "Default")
      (node (ref "U$17") (pin "1") (pinfunction "0_1") (pintype "passive"))
    )
    (net (code "111") (name "unconnected-(U$17-1-Pad4)") (class "Default")
      (node (ref "U$17") (pin "4") (pinfunction "1_4") (pintype "passive"))
    )
    (net (code "112") (name "unconnected-(U$24-0-Pad1)") (class "Default")
      (node (ref "U$24") (pin "1") (pinfunction "0_1") (pintype "passive"))
    )
    (net (code "113") (name "unconnected-(U$24-1-Pad4)") (class "Default")
      (node (ref "U$24") (pin "4") (pinfunction "1_4") (pintype "passive"))
    )
    (net (code "114") (name "unconnected-(U2-CLKOUT-Pad6)") (class "Default")
      (node (ref "U2") (pin "6") (pinfunction "CLKOUT_6") (pintype "output"))
    )
    (net (code "115") (name "unconnected-(U2-NC-Pad1)") (class "Default")
      (node (ref "U2") (pin "1") (pinfunction "NC_1") (pintype "no_connect"))
    )
    (net (code "116") (name "unconnected-(U3-INT2-Pad9)") (class "Default")
      (node (ref "U3") (pin "9") (pinfunction "INT2_9") (pintype "bidirectional"))
    )
    (net (code "117") (name "unconnected-(U3-NC-Pad11)") (class "Default")
      (node (ref "U3") (pin "11") (pinfunction "NC_11") (pintype "bidirectional"))
    )
    (net (code "118") (name "unconnected-(U3-OCS-Pad10)") (class "Default")
      (node (ref "U3") (pin "10") (pinfunction "OCS_10") (pintype "bidirectional"))
    )
    (net (code "119") (name "unconnected-(U4-S4A-Pad12)") (class "Default")
      (node (ref "U4") (pin "12") (pinfunction "S4A_12") (pintype "bidirectional"))
    )
    (net (code "120") (name "unconnected-(U4-S4B-Pad11)") (class "Default")
      (node (ref "U4") (pin "11") (pinfunction "S4B_11") (pintype "bidirectional"))
    )
    (net (code "121") (name "unconnected-(U9-BP-Pad4)") (class "Default")
      (node (ref "U9") (pin "4") (pinfunction "BP_4") (pintype "input"))
    )
  )
)
